# io_module.net
KiCad netlist of a schematic drawn in EAGLE
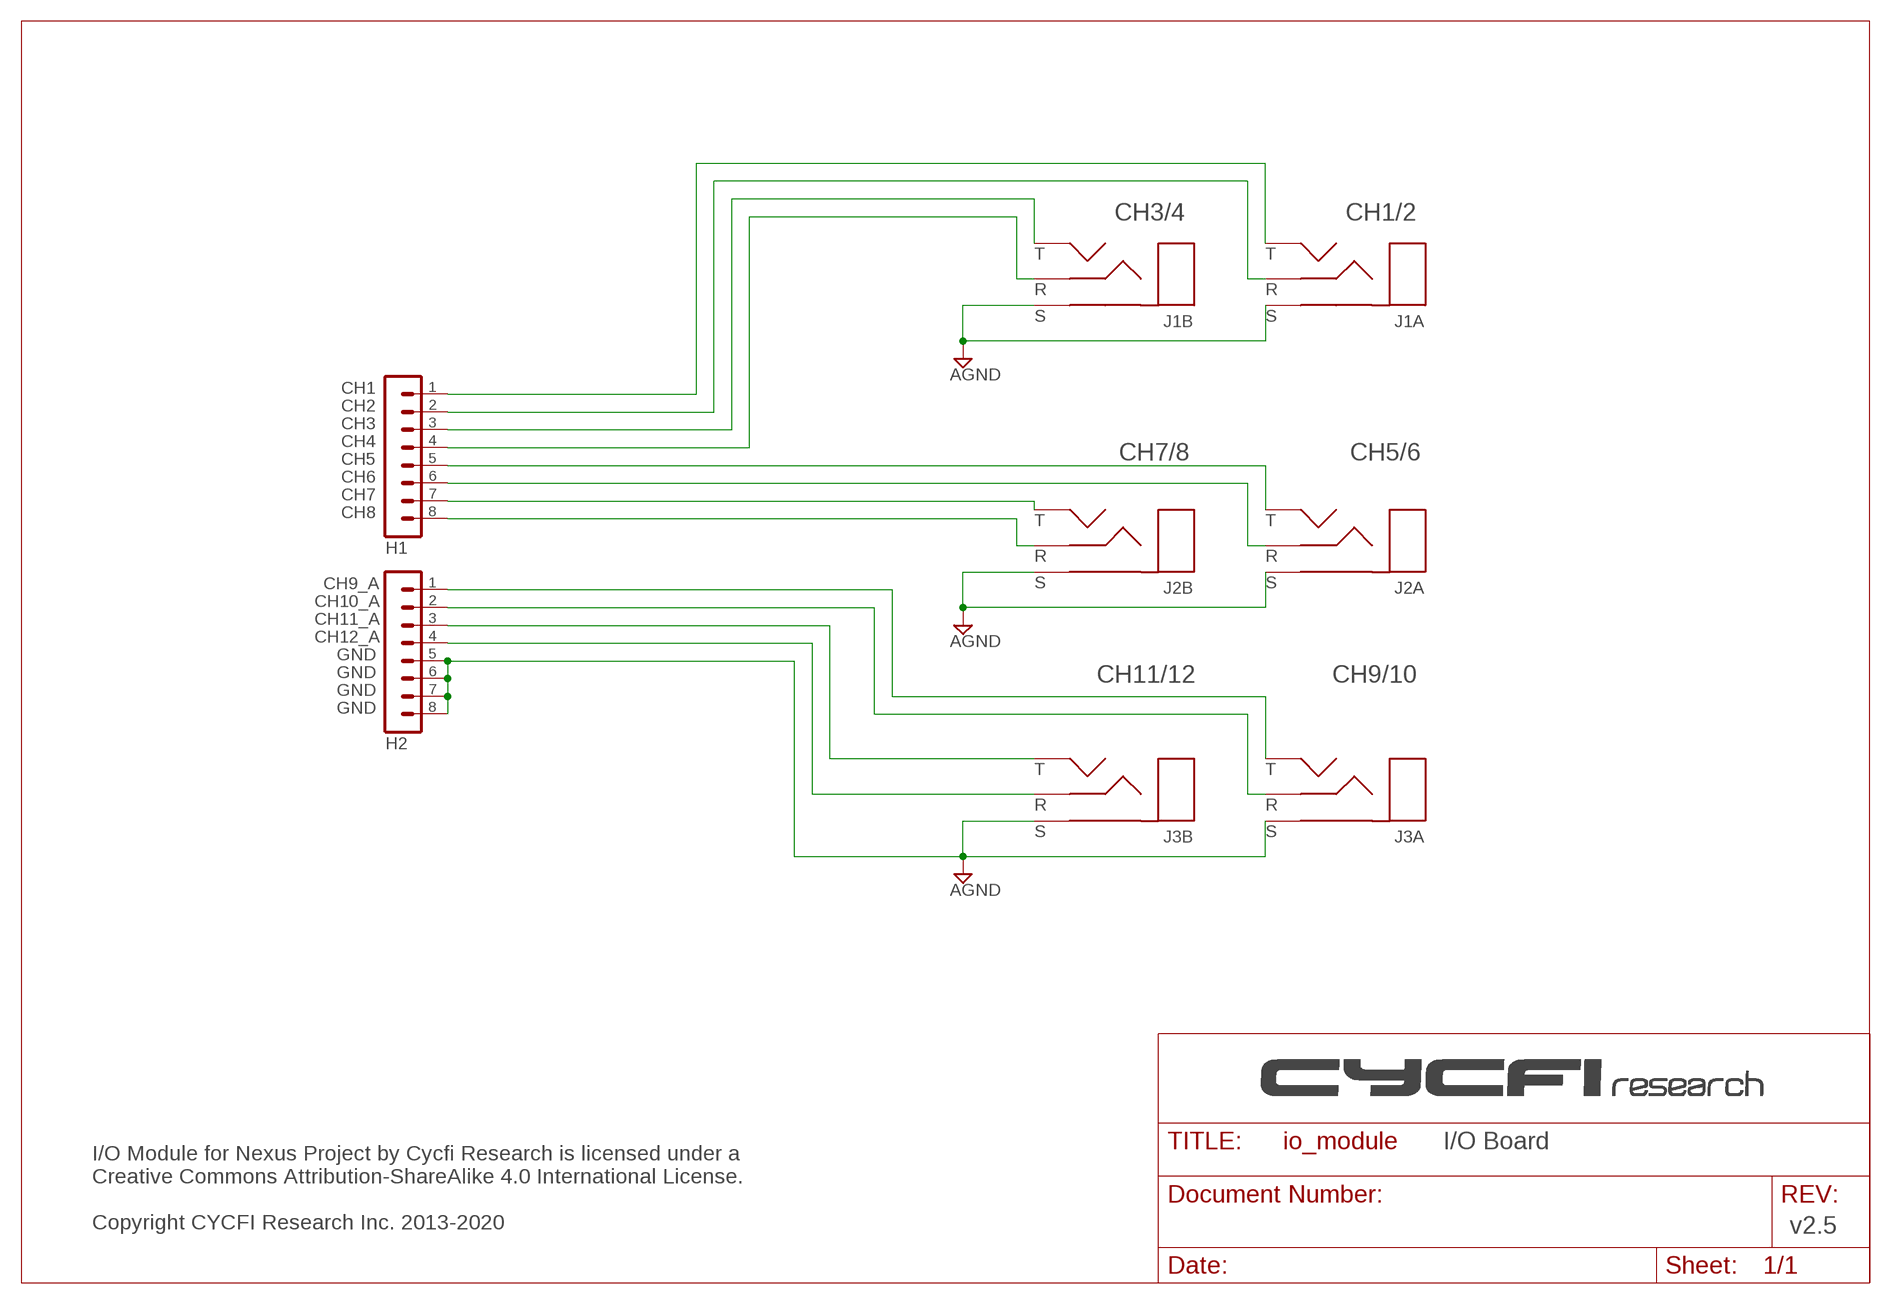
[diagram p0: schematic, sheet 1]

(export (version "E")
  (design (tool "Eeschema 10.0.6"))
  (components
    (comp (ref "H1")
      (value "MA08-1")
      (footprint "eagle-import:MA08-1")
      (libsource (lib "eagle-import") (part "MA08-1"))
    )
    (comp (ref "H2")
      (value "MA08-1")
      (footprint "eagle-import:MA08-1")
      (libsource (lib "eagle-import") (part "MA08-1"))
    )
    (comp (ref "J1")
      (value "ZHEJINAG_CK_STSJACKS")
      (footprint "eagle-import:ZHEJINAG_CK_6.35")
      (libsource (lib "eagle-import") (part "ZHEJINAG_CK_STSJACKS"))
    )
    (comp (ref "J2")
      (value "ZHEJINAG_CK_STSJACKS")
      (footprint "eagle-import:ZHEJINAG_CK_6.35")
      (libsource (lib "eagle-import") (part "ZHEJINAG_CK_STSJACKS"))
    )
    (comp (ref "J3")
      (value "ZHEJINAG_CK_STSJACKS")
      (footprint "eagle-import:ZHEJINAG_CK_6.35")
      (libsource (lib "eagle-import") (part "ZHEJINAG_CK_STSJACKS"))
    )
  )
  (nets
    (net (code "1") (name "AGND") (class "Default")
      (node (ref "H2") (pin "5") (pinfunction "5_5") (pintype "passive"))
      (node (ref "H2") (pin "6") (pinfunction "6_6") (pintype "passive"))
      (node (ref "H2") (pin "7") (pinfunction "7_7") (pintype "passive"))
      (node (ref "H2") (pin "8") (pinfunction "8_8") (pintype "passive"))
      (node (ref "J1") (pin "2S") (pinfunction "S_2S") (pintype "bidirectional"))
      (node (ref "J1") (pin "S") (pinfunction "S_S") (pintype "bidirectional"))
      (node (ref "J2") (pin "2S") (pinfunction "S_2S") (pintype "bidirectional"))
      (node (ref "J2") (pin "S") (pinfunction "S_S") (pintype "bidirectional"))
      (node (ref "J3") (pin "2S") (pinfunction "S_2S") (pintype "bidirectional"))
      (node (ref "J3") (pin "S") (pinfunction "S_S") (pintype "bidirectional"))
    )
    (net (code "2") (name "Net-(H1-Pad3)") (class "Default")
      (node (ref "H1") (pin "3") (pinfunction "3_3") (pintype "passive"))
      (node (ref "J1") (pin "T") (pinfunction "T_T") (pintype "bidirectional"))
    )
    (net (code "3") (name "Net-(H1-Pad4)") (class "Default")
      (node (ref "H1") (pin "4") (pinfunction "4_4") (pintype "passive"))
      (node (ref "J1") (pin "R") (pinfunction "R_R") (pintype "bidirectional"))
    )
    (net (code "4") (name "Net-(H1-Pad7)") (class "Default")
      (node (ref "H1") (pin "7") (pinfunction "7_7") (pintype "passive"))
      (node (ref "J2") (pin "T") (pinfunction "T_T") (pintype "bidirectional"))
    )
    (net (code "5") (name "Net-(H1-Pad8)") (class "Default")
      (node (ref "H1") (pin "8") (pinfunction "8_8") (pintype "passive"))
      (node (ref "J2") (pin "R") (pinfunction "R_R") (pintype "bidirectional"))
    )
    (net (code "6") (name "Net-(H2-Pad3)") (class "Default")
      (node (ref "H2") (pin "3") (pinfunction "3_3") (pintype "passive"))
      (node (ref "J3") (pin "T") (pinfunction "T_T") (pintype "bidirectional"))
    )
    (net (code "7") (name "Net-(H2-Pad4)") (class "Default")
      (node (ref "H2") (pin "4") (pinfunction "4_4") (pintype "passive"))
      (node (ref "J3") (pin "R") (pinfunction "R_R") (pintype "bidirectional"))
    )
    (net (code "8") (name "Net-(J1A-R)") (class "Default")
      (node (ref "H1") (pin "2") (pinfunction "2_2") (pintype "passive"))
      (node (ref "J1") (pin "2R") (pinfunction "R_2R") (pintype "bidirectional"))
    )
    (net (code "9") (name "Net-(J1A-T)") (class "Default")
      (node (ref "H1") (pin "1") (pinfunction "1_1") (pintype "passive"))
      (node (ref "J1") (pin "2T") (pinfunction "T_2T") (pintype "bidirectional"))
    )
    (net (code "10") (name "Net-(J2A-R)") (class "Default")
      (node (ref "H1") (pin "6") (pinfunction "6_6") (pintype "passive"))
      (node (ref "J2") (pin "2R") (pinfunction "R_2R") (pintype "bidirectional"))
    )
    (net (code "11") (name "Net-(J2A-T)") (class "Default")
      (node (ref "H1") (pin "5") (pinfunction "5_5") (pintype "passive"))
      (node (ref "J2") (pin "2T") (pinfunction "T_2T") (pintype "bidirectional"))
    )
    (net (code "12") (name "Net-(J3A-R)") (class "Default")
      (node (ref "H2") (pin "2") (pinfunction "2_2") (pintype "passive"))
      (node (ref "J3") (pin "2R") (pinfunction "R_2R") (pintype "bidirectional"))
    )
    (net (code "13") (name "Net-(J3A-T)") (class "Default")
      (node (ref "H2") (pin "1") (pinfunction "1_1") (pintype "passive"))
      (node (ref "J3") (pin "2T") (pinfunction "T_2T") (pintype "bidirectional"))
    )
  )
)
